# CurrentLimiter.net
KiCad netlist of a schematic drawn in Altium Designer
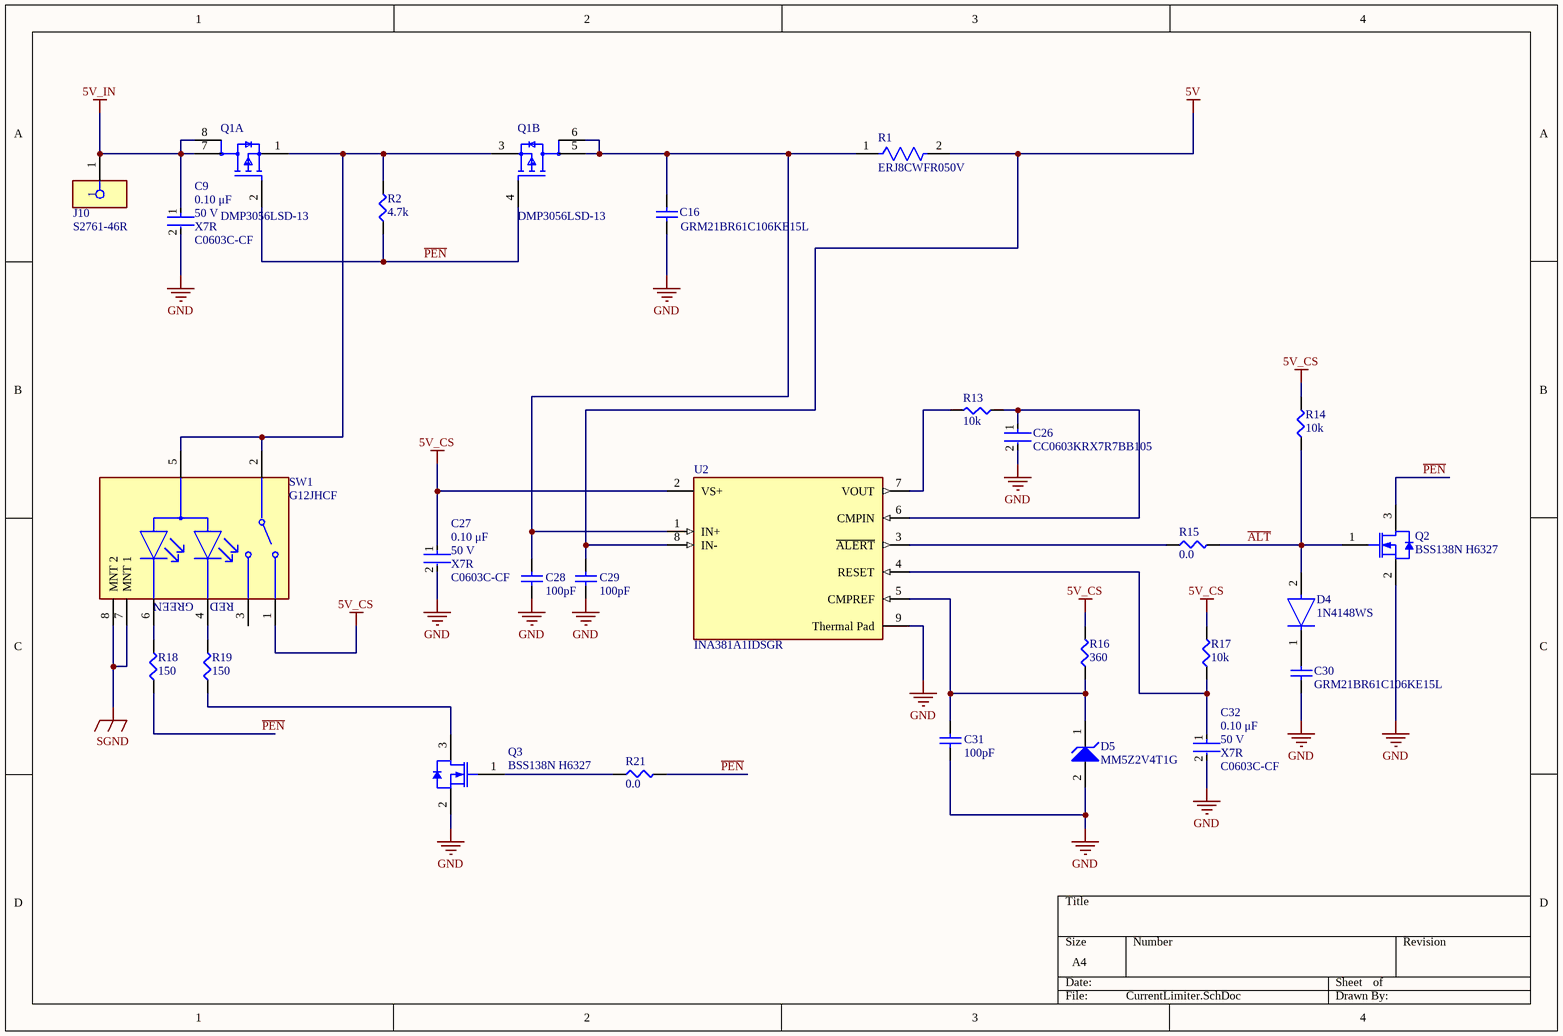
[diagram p0: CurrentLimiter.SchDoc]

(export (version "E")
  (design (tool "Eeschema 10.0.6"))
  (components
    (comp (ref "C9")
      (value "0.10 μF")
      (footprint "FP-C0603C-CF-MFG")
      (description "CAP CER 0.1UF 50V X7R 0603")
      (fields
        (field (name "TOLERANCE") "0.1")
        (field (name "MANUFACTURER") "KEMET")
        (field (name "PACKAGE") "C0603C-CF")
        (field (name "VOLTAGE RATING") "50 V")
        (field (name "TEMPERATURE CHARACTERISTIC") "X7R")
      )
      (libsource (lib "Altium Content Vault") (part "b4654b650e69147ec39a6b967a45e02"))
    )
    (comp (ref "C16")
      (value "GRM21BR61C106KE15L")
      (footprint "CAPC2013X135X50LL10T20")
      (fields (field (name "MANUFACTURER") "Murata"))
      (libsource (lib "Altium Content Vault") (part "CAP"))
    )
    (comp (ref "C26")
      (value "CC0603KRX7R7BB105")
      (footprint "FP-CC0603-DA-MFG")
      (description "CC0603 1 uF X7R 10.00% 16 V")
      (fields (field (name "TOLERANCE") "0.1"))
      (libsource (lib "Altium Content Vault") (part "11868f565c42a9108669ba33697ecf6"))
    )
    (comp (ref "C27")
      (value "0.10 μF")
      (footprint "FP-C0603C-CF-MFG")
      (description "CAP CER 0.1UF 50V X7R 0603")
      (fields
        (field (name "TOLERANCE") "0.1")
        (field (name "MANUFACTURER") "KEMET")
        (field (name "PACKAGE") "C0603C-CF")
        (field (name "VOLTAGE RATING") "50 V")
        (field (name "TEMPERATURE CHARACTERISTIC") "X7R")
      )
      (libsource (lib "Altium Content Vault") (part "b4654b650e69147ec39a6b967a45e02"))
    )
    (comp (ref "C28")
      (value "CC0603JRNPO9BN101")
      (footprint "CAPC1608X90X40ML10T20")
      (description "Chip Capacitor, 100 pF, +/- 5%, 50 V, -55 to 125 degC, 0603 (1608 Metric), RoHS, Tape and Reel")
      (fields
        (field (name "TOLERANCE") "5%")
        (field (name "CAPACITANCE") "100pF")
        (field (name "VOLTAGE") "50V")
      )
      (libsource (lib "Altium Content Vault") (part "CAP-NP-2"))
    )
    (comp (ref "C29")
      (value "CC0603JRNPO9BN101")
      (footprint "CAPC1608X90X40ML10T20")
      (description "Chip Capacitor, 100 pF, +/- 5%, 50 V, -55 to 125 degC, 0603 (1608 Metric), RoHS, Tape and Reel")
      (fields
        (field (name "TOLERANCE") "5%")
        (field (name "CAPACITANCE") "100pF")
        (field (name "VOLTAGE") "50V")
      )
      (libsource (lib "Altium Content Vault") (part "CAP-NP-2"))
    )
    (comp (ref "C30")
      (value "GRM21BR61C106KE15L")
      (footprint "CAPC2013X135X50LL10T20")
      (fields (field (name "MANUFACTURER") "Murata"))
      (libsource (lib "Altium Content Vault") (part "CAP"))
    )
    (comp (ref "C31")
      (value "CC0603JRNPO9BN101")
      (footprint "CAPC1608X90X40ML10T20")
      (description "Chip Capacitor, 100 pF, +/- 5%, 50 V, -55 to 125 degC, 0603 (1608 Metric), RoHS, Tape and Reel")
      (fields
        (field (name "TOLERANCE") "5%")
        (field (name "CAPACITANCE") "100pF")
        (field (name "VOLTAGE") "50V")
      )
      (libsource (lib "Altium Content Vault") (part "CAP-NP-2"))
    )
    (comp (ref "C32")
      (value "0.10 μF")
      (footprint "FP-C0603C-CF-MFG")
      (description "CAP CER 0.1UF 50V X7R 0603")
      (fields
        (field (name "TOLERANCE") "0.1")
        (field (name "MANUFACTURER") "KEMET")
        (field (name "PACKAGE") "C0603C-CF")
        (field (name "VOLTAGE RATING") "50 V")
        (field (name "TEMPERATURE CHARACTERISTIC") "X7R")
      )
      (libsource (lib "Altium Content Vault") (part "b4654b650e69147ec39a6b967a45e02"))
    )
    (comp (ref "D4")
      (value "1N4148WS")
      (footprint "FP-477AB-IPC_C")
      (description "DIODE GEN PURP 75V 150MA SOD323F")
      (libsource (lib "Altium Content Vault") (part "d7152d700b627762746794eb795d46e"))
    )
    (comp (ref "D5")
      (value "MM5Z2V4T1G")
      (footprint "ONSC-SOD-523-2-502-01_V")
      (description "Zener Voltage Regulator, 500 mW, 2-Pin SOD-523, Pb-Free, Tape and Reel")
      (fields (field (name "MANUFACTURER") "On Semiconductor"))
      (libsource (lib "Altium Content Vault") (part "ONSC-K1A2-2"))
    )
    (comp (ref "J10")
      (value "S2761-46R")
      (footprint "FP-S2761-46R-MFG")
      (description "PC TEST POINT NATURAL")
      (libsource (lib "Altium Content Vault") (part "98815daf2f2c152b0c43f5ab9800df6"))
    )
    (comp (ref "Q1")
      (value "DMP3056LSD-13")
      (footprint "FP-SO-8-MFG")
      (description "MOSFET 2P-CH 30V 6.9A 8-SOIC")
      (libsource (lib "Altium Content Vault") (part "0b7cfba55612a68638ef08d790250c5"))
    )
    (comp (ref "Q2")
      (value "BSS138N H6327")
      (footprint "INF-PG-SOT-23-3_V")
      (description "N-Channel Small Signal MOSFET, 60 VDS, 0.23 A, -55 to 150 degC, 3-Pin SOT-23, RoHS, Tape and Reel")
      (fields (field (name "MANUFACTURER") "InfineonTechnologiesAmericasInc."))
      (libsource (lib "Altium Content Vault") (part "NDMOS-GSD-3"))
    )
    (comp (ref "Q3")
      (value "BSS138N H6327")
      (footprint "INF-PG-SOT-23-3_V")
      (description "N-Channel Small Signal MOSFET, 60 VDS, 0.23 A, -55 to 150 degC, 3-Pin SOT-23, RoHS, Tape and Reel")
      (fields (field (name "MANUFACTURER") "InfineonTechnologiesAmericasInc."))
      (libsource (lib "Altium Content Vault") (part "NDMOS-GSD-3"))
    )
    (comp (ref "R1")
      (value "ERJ8CWFR050V")
      (footprint "FP-ERJ8CW-IPC_B")
      (description "RES 0.05 OHM 1% 1W 1206")
      (libsource (lib "Altium Content Vault") (part "1029c3af85768c4190bb7ad29bc67b5"))
    )
    (comp (ref "R2")
      (value "4.7k")
      (footprint "SMD-0603-RES")
      (description "RES SMD 4.7K OHM 1% 1/10W 0603")
      (fields
        (field (name "PART NUMBER") "ERJ-3EKF4701V")
        (field (name "DIGI-KEY PART NUMBER") "P4.70KHCT-ND")
      )
      (libsource (lib "Panasonic_ERJ_0603") (part "ERJ-3EKF4701V"))
    )
    (comp (ref "R13")
      (value "10k")
      (footprint "SMD-0603-RES")
      (description "RES SMD 10K OHM 1% 1/10W 0603")
      (fields
        (field (name "PART NUMBER") "ERJ-3EKF1002V")
        (field (name "DIGI-KEY PART NUMBER") "P10.0KHCT-ND")
      )
      (libsource (lib "Panasonic_ERJ_0603") (part "ERJ-3EKF1002V"))
    )
    (comp (ref "R14")
      (value "10k")
      (footprint "SMD-0603-RES")
      (description "RES SMD 10K OHM 1% 1/10W 0603")
      (fields
        (field (name "PART NUMBER") "ERJ-3EKF1002V")
        (field (name "DIGI-KEY PART NUMBER") "P10.0KHCT-ND")
      )
      (libsource (lib "Panasonic_ERJ_0603") (part "ERJ-3EKF1002V"))
    )
    (comp (ref "R15")
      (value "0.0")
      (footprint "SMD-0603-RES")
      (description "RES SMD 0.0OHM JUMPER 1/10W 0603")
      (fields (field (name "PART NUMBER") "ERJ-3GEY0R00V") (field (name "DIGI-KEY PART NUMBER") "P0.0GCT-ND"))
      (libsource (lib "Panasonic_ERJ_0603") (part "ERJ-3GEY0R00V"))
    )
    (comp (ref "R16")
      (value "360")
      (footprint "SMD-0603-RES")
      (description "RES SMD 360 OHM 1% 1/10W 0603")
      (fields (field (name "PART NUMBER") "ERJ-3EKF3600V") (field (name "DIGI-KEY PART NUMBER") "P360HCT-ND"))
      (libsource (lib "Panasonic_ERJ_0603") (part "ERJ-3EKF3600V"))
    )
    (comp (ref "R17")
      (value "10k")
      (footprint "SMD-0603-RES")
      (description "RES SMD 10K OHM 1% 1/10W 0603")
      (fields
        (field (name "PART NUMBER") "ERJ-3EKF1002V")
        (field (name "DIGI-KEY PART NUMBER") "P10.0KHCT-ND")
      )
      (libsource (lib "Panasonic_ERJ_0603") (part "ERJ-3EKF1002V"))
    )
    (comp (ref "R18")
      (value "150")
      (footprint "SMD-0603-RES")
      (description "RES SMD 150 OHM 1% 1/10W 0603")
      (fields (field (name "PART NUMBER") "ERJ-3EKF1500V") (field (name "DIGI-KEY PART NUMBER") "P150HCT-ND"))
      (libsource (lib "Panasonic_ERJ_0603") (part "ERJ-3EKF1500V"))
    )
    (comp (ref "R19")
      (value "150")
      (footprint "SMD-0603-RES")
      (description "RES SMD 150 OHM 1% 1/10W 0603")
      (fields (field (name "PART NUMBER") "ERJ-3EKF1500V") (field (name "DIGI-KEY PART NUMBER") "P150HCT-ND"))
      (libsource (lib "Panasonic_ERJ_0603") (part "ERJ-3EKF1500V"))
    )
    (comp (ref "R21")
      (value "0.0")
      (footprint "SMD-0603-RES")
      (description "RES SMD 0.0OHM JUMPER 1/10W 0603")
      (fields (field (name "PART NUMBER") "ERJ-3GEY0R00V") (field (name "DIGI-KEY PART NUMBER") "P0.0GCT-ND"))
      (libsource (lib "Panasonic_ERJ_0603") (part "ERJ-3GEY0R00V"))
    )
    (comp (ref "SW1")
      (value "G12JHCF")
      (footprint "FP-G12JHCF-MFG")
      (description "SWITCH TOGGLE SPDT 0.4VA 28V")
      (libsource (lib "Altium Content Vault") (part "5ce0e523df4838859c466eabae3a0ce"))
    )
    (comp (ref "U2")
      (value "INA381A1IDSGR")
      (footprint "FP-DSG0008A-IPC_A")
      (description "LOW COST CURRENT SENSOR WITH COM")
      (libsource (lib "Altium Content Vault") (part "23e9e498bafd5ea70f1779a62eea11d"))
    )
  )
  (nets
    (net (code "1") (name "/~{ALT}") (class "Default")
      (node (ref "D4") (pin "2") (pinfunction "A_2") (pintype "passive"))
      (node (ref "Q2") (pin "1") (pinfunction "GATE_1") (pintype "passive"))
      (node (ref "R14") (pin "1") (pinfunction "1_1") (pintype "passive"))
      (node (ref "R15") (pin "2") (pinfunction "2_2") (pintype "passive"))
    )
    (net (code "2") (name "/~{PEN}") (class "Default")
      (node (ref "Q1") (pin "2") (pinfunction "G1_2") (pintype "passive"))
      (node (ref "Q1") (pin "4") (pinfunction "G2_4") (pintype "passive"))
      (node (ref "Q2") (pin "3") (pinfunction "DRAIN_3") (pintype "passive"))
      (node (ref "R18") (pin "1") (pinfunction "1_1") (pintype "passive"))
      (node (ref "R2") (pin "1") (pinfunction "1_1") (pintype "passive"))
      (node (ref "R21") (pin "2") (pinfunction "2_2") (pintype "passive"))
    )
    (net (code "3") (name "5V") (class "Default")
      (node (ref "C29") (pin "2") (pinfunction "2_2") (pintype "passive"))
      (node (ref "R1") (pin "2") (pinfunction "2_2") (pintype "passive"))
      (node (ref "U2") (pin "8") (pinfunction "IN-_8") (pintype "input"))
    )
    (net (code "4") (name "5V_CS") (class "Default")
      (node (ref "C27") (pin "1") (pinfunction "1_1") (pintype "passive"))
      (node (ref "R14") (pin "2") (pinfunction "2_2") (pintype "passive"))
      (node (ref "R16") (pin "2") (pinfunction "2_2") (pintype "passive"))
      (node (ref "R17") (pin "2") (pinfunction "2_2") (pintype "passive"))
      (node (ref "SW1") (pin "1") (pinfunction "1_1") (pintype "passive"))
      (node (ref "U2") (pin "2") (pinfunction "VS+_2") (pintype "power_in"))
    )
    (net (code "5") (name "5V_IN") (class "Default")
      (node (ref "C9") (pin "1") (pinfunction "1_1") (pintype "passive"))
      (node (ref "J10") (pin "1") (pinfunction "1_1") (pintype "passive"))
      (node (ref "Q1") (pin "7") (pinfunction "D1_7") (pintype "passive"))
      (node (ref "Q1") (pin "8") (pinfunction "D1_8") (pintype "passive"))
    )
    (net (code "6") (name "GND") (class "Default")
      (node (ref "C16") (pin "1") (pinfunction "1_1") (pintype "passive"))
      (node (ref "C26") (pin "2") (pinfunction "2_2") (pintype "passive"))
      (node (ref "C27") (pin "2") (pinfunction "2_2") (pintype "passive"))
      (node (ref "C28") (pin "1") (pinfunction "1_1") (pintype "passive"))
      (node (ref "C29") (pin "1") (pinfunction "1_1") (pintype "passive"))
      (node (ref "C30") (pin "1") (pinfunction "1_1") (pintype "passive"))
      (node (ref "C31") (pin "1") (pinfunction "1_1") (pintype "passive"))
      (node (ref "C32") (pin "2") (pinfunction "2_2") (pintype "passive"))
      (node (ref "C9") (pin "2") (pinfunction "2_2") (pintype "passive"))
      (node (ref "D5") (pin "2") (pinfunction "A_2") (pintype "passive"))
      (node (ref "Q2") (pin "2") (pinfunction "SOURCE_2") (pintype "passive"))
      (node (ref "Q3") (pin "2") (pinfunction "SOURCE_2") (pintype "passive"))
      (node (ref "U2") (pin "9") (pinfunction "Thermal_Pad_9") (pintype "power_in"))
    )
    (net (code "7") (name "Net-(D4-C)") (class "Default")
      (node (ref "C30") (pin "2") (pinfunction "2_2") (pintype "passive"))
      (node (ref "D4") (pin "1") (pinfunction "C_1") (pintype "passive"))
    )
    (net (code "8") (name "Net-(D5-K)") (class "Default")
      (node (ref "C31") (pin "2") (pinfunction "2_2") (pintype "passive"))
      (node (ref "D5") (pin "1") (pinfunction "K_1") (pintype "passive"))
      (node (ref "R16") (pin "1") (pinfunction "1_1") (pintype "passive"))
      (node (ref "U2") (pin "5") (pinfunction "CMPREF_5") (pintype "input"))
    )
    (net (code "9") (name "Net-(Q1A-S1)") (class "Default")
      (node (ref "Q1") (pin "1") (pinfunction "S1_1") (pintype "passive"))
      (node (ref "Q1") (pin "3") (pinfunction "S2_3") (pintype "passive"))
      (node (ref "R2") (pin "2") (pinfunction "2_2") (pintype "passive"))
      (node (ref "SW1") (pin "2") (pinfunction "COM_2") (pintype "passive"))
      (node (ref "SW1") (pin "5") (pinfunction "A_5") (pintype "passive"))
    )
    (net (code "10") (name "Net-(Q3-DRAIN)") (class "Default")
      (node (ref "Q3") (pin "3") (pinfunction "DRAIN_3") (pintype "passive"))
      (node (ref "R19") (pin "1") (pinfunction "1_1") (pintype "passive"))
    )
    (net (code "11") (name "Net-(Q3-GATE)") (class "Default")
      (node (ref "Q3") (pin "1") (pinfunction "GATE_1") (pintype "passive"))
      (node (ref "R21") (pin "1") (pinfunction "1_1") (pintype "passive"))
    )
    (net (code "12") (name "Net-(SW1-GREEN_C)") (class "Default")
      (node (ref "R18") (pin "2") (pinfunction "2_2") (pintype "passive"))
      (node (ref "SW1") (pin "6") (pinfunction "GREEN_C_6") (pintype "passive"))
    )
    (net (code "13") (name "Net-(SW1-RED_C)") (class "Default")
      (node (ref "R19") (pin "2") (pinfunction "2_2") (pintype "passive"))
      (node (ref "SW1") (pin "4") (pinfunction "RED_C_4") (pintype "passive"))
    )
    (net (code "14") (name "Net-(U2-CMPIN)") (class "Default")
      (node (ref "C26") (pin "1") (pinfunction "1_1") (pintype "passive"))
      (node (ref "R13") (pin "1") (pinfunction "1_1") (pintype "passive"))
      (node (ref "U2") (pin "6") (pinfunction "CMPIN_6") (pintype "input"))
    )
    (net (code "15") (name "Net-(U2-IN+)") (class "Default")
      (node (ref "C16") (pin "2") (pinfunction "2_2") (pintype "passive"))
      (node (ref "C28") (pin "2") (pinfunction "2_2") (pintype "passive"))
      (node (ref "Q1") (pin "5") (pinfunction "D2_5") (pintype "passive"))
      (node (ref "Q1") (pin "6") (pinfunction "D2_6") (pintype "passive"))
      (node (ref "R1") (pin "1") (pinfunction "1_1") (pintype "passive"))
      (node (ref "U2") (pin "1") (pinfunction "IN+_1") (pintype "input"))
    )
    (net (code "16") (name "Net-(U2-RESET)") (class "Default")
      (node (ref "C32") (pin "1") (pinfunction "1_1") (pintype "passive"))
      (node (ref "R17") (pin "1") (pinfunction "1_1") (pintype "passive"))
      (node (ref "U2") (pin "4") (pinfunction "RESET_4") (pintype "input"))
    )
    (net (code "17") (name "Net-(U2-VOUT)") (class "Default")
      (node (ref "R13") (pin "2") (pinfunction "2_2") (pintype "passive"))
      (node (ref "U2") (pin "7") (pinfunction "VOUT_7") (pintype "output"))
    )
    (net (code "18") (name "Net-(U2-~{ALERT})") (class "Default")
      (node (ref "R15") (pin "1") (pinfunction "1_1") (pintype "passive"))
      (node (ref "U2") (pin "3") (pinfunction "~{ALERT}_3") (pintype "output"))
    )
    (net (code "19") (name "SGND") (class "Default")
      (node (ref "SW1") (pin "7") (pinfunction "MNT_1_7") (pintype "passive"))
      (node (ref "SW1") (pin "8") (pinfunction "MNT_2_8") (pintype "passive"))
    )
    (net (code "20") (name "unconnected-(SW1-Pad3)") (class "Default")
      (node (ref "SW1") (pin "3") (pinfunction "3_3") (pintype "passive"))
    )
  )
)
